# Reid_Orthotic_v2_MUX.net
KiCad netlist of a schematic drawn in Altium Designer
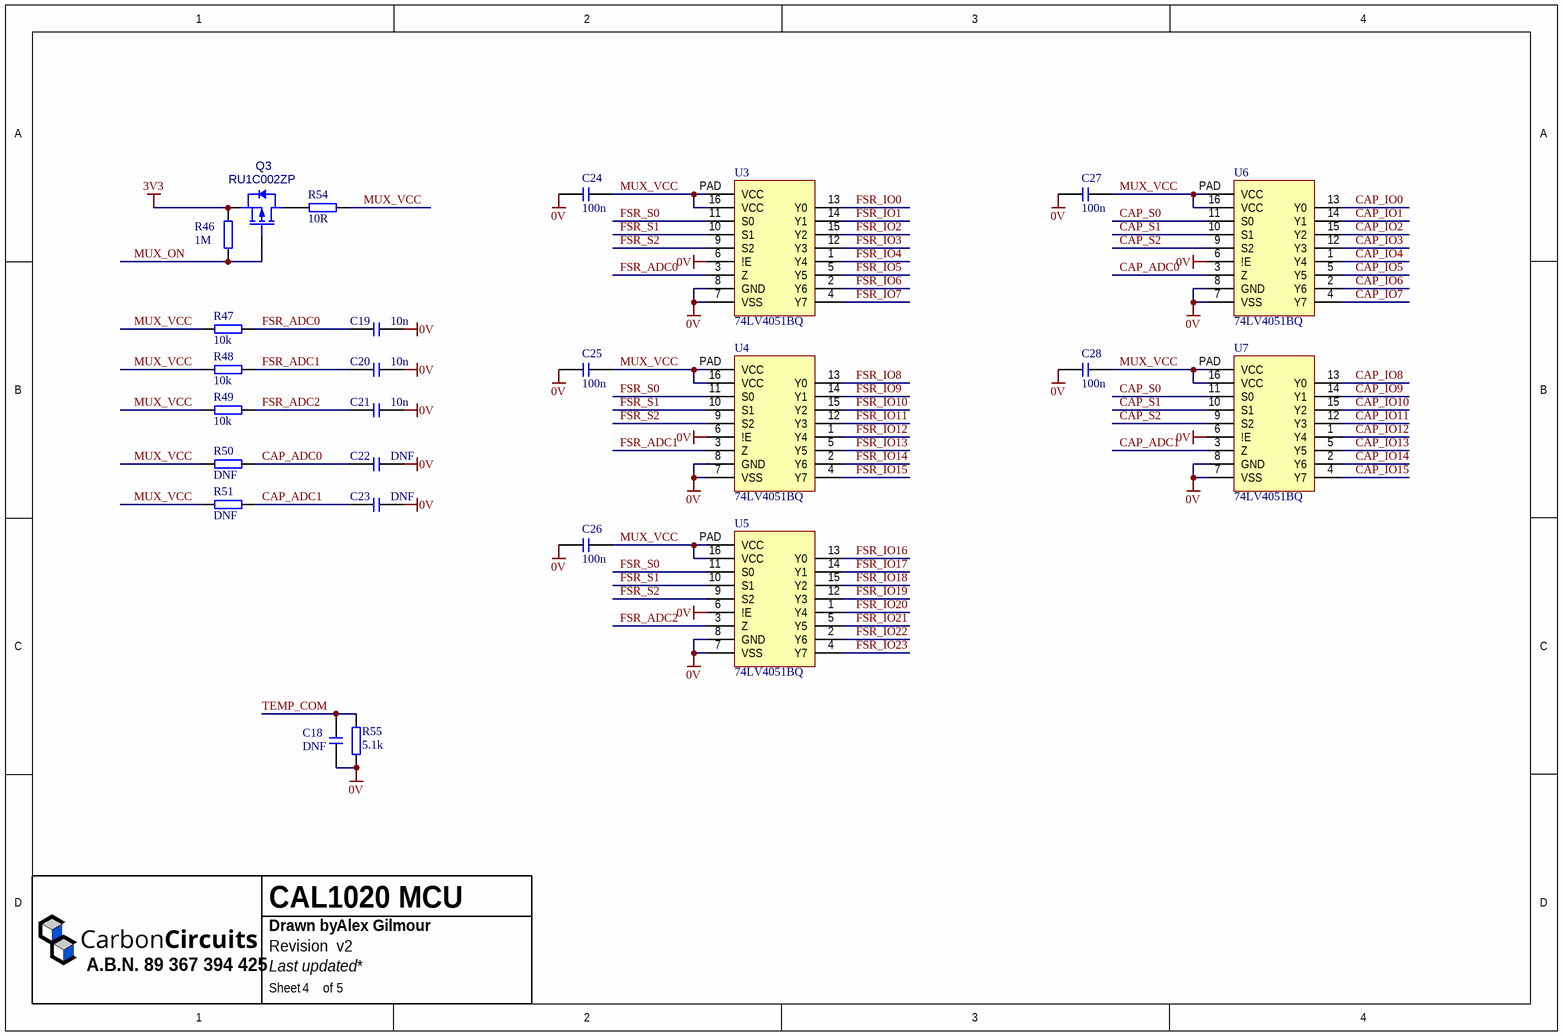
[diagram p0: Reid Orthotic v2 MUX.SchDoc]

(export (version "E")
  (design (tool "Eeschema 10.0.6"))
  (components
    (comp (ref "C18")
      (value "DNF")
      (footprint "0402 CAP HD")
      (libsource (lib "zoo589 PCB Library") (part "Capacitor"))
    )
    (comp (ref "C19")
      (value "10n")
      (footprint "0402 CAP HD")
      (libsource (lib "zoo589 PCB Library") (part "Capacitor"))
    )
    (comp (ref "C20")
      (value "10n")
      (footprint "0402 CAP HD")
      (libsource (lib "zoo589 PCB Library") (part "Capacitor"))
    )
    (comp (ref "C21")
      (value "10n")
      (footprint "0402 CAP HD")
      (libsource (lib "zoo589 PCB Library") (part "Capacitor"))
    )
    (comp (ref "C22")
      (value "DNF")
      (footprint "0402 CAP HD")
      (libsource (lib "zoo589 PCB Library") (part "Capacitor"))
    )
    (comp (ref "C23")
      (value "DNF")
      (footprint "0402 CAP HD")
      (libsource (lib "zoo589 PCB Library") (part "Capacitor"))
    )
    (comp (ref "C24")
      (value "100n")
      (footprint "0402 CAP HD")
      (libsource (lib "zoo589 PCB Library") (part "Capacitor"))
    )
    (comp (ref "C25")
      (value "100n")
      (footprint "0402 CAP HD")
      (libsource (lib "zoo589 PCB Library") (part "Capacitor"))
    )
    (comp (ref "C26")
      (value "100n")
      (footprint "0402 CAP HD")
      (libsource (lib "zoo589 PCB Library") (part "Capacitor"))
    )
    (comp (ref "C27")
      (value "100n")
      (footprint "0402 CAP HD")
      (libsource (lib "zoo589 PCB Library") (part "Capacitor"))
    )
    (comp (ref "C28")
      (value "100n")
      (footprint "0402 CAP HD")
      (libsource (lib "zoo589 PCB Library") (part "Capacitor"))
    )
    (comp (ref "Q3")
      (value "RU1C002ZP")
      (footprint "SOT323")
      (libsource (lib "zoo589 PCB Library") (part "MOSFET PCH"))
    )
    (comp (ref "R46")
      (value "1M")
      (footprint "0402 RES HD")
      (libsource (lib "zoo589 PCB Library") (part "Resistor"))
    )
    (comp (ref "R47")
      (value "10k")
      (footprint "0402 RES HD")
      (libsource (lib "zoo589 PCB Library") (part "Resistor"))
    )
    (comp (ref "R48")
      (value "10k")
      (footprint "0402 RES HD")
      (libsource (lib "zoo589 PCB Library") (part "Resistor"))
    )
    (comp (ref "R49")
      (value "10k")
      (footprint "0402 RES HD")
      (libsource (lib "zoo589 PCB Library") (part "Resistor"))
    )
    (comp (ref "R50")
      (value "DNF")
      (footprint "0402 RES HD")
      (libsource (lib "zoo589 PCB Library") (part "Resistor"))
    )
    (comp (ref "R51")
      (value "DNF")
      (footprint "0402 RES HD")
      (libsource (lib "zoo589 PCB Library") (part "Resistor"))
    )
    (comp (ref "R54")
      (value "10R")
      (footprint "0603 RES HD")
      (libsource (lib "zoo589 PCB Library") (part "Resistor"))
    )
    (comp (ref "R55")
      (value "5.1k")
      (footprint "0402 RES HD")
      (libsource (lib "zoo589 PCB Library") (part "Resistor"))
    )
    (comp (ref "U3")
      (value "74LV4051BQ")
      (footprint "74LV4051BQ")
      (libsource (lib "CarbonCircuits Part Library") (part "74HC4051BQ"))
    )
    (comp (ref "U4")
      (value "74LV4051BQ")
      (footprint "74LV4051BQ")
      (libsource (lib "CarbonCircuits Part Library") (part "74HC4051BQ"))
    )
    (comp (ref "U5")
      (value "74LV4051BQ")
      (footprint "74LV4051BQ")
      (libsource (lib "CarbonCircuits Part Library") (part "74HC4051BQ"))
    )
    (comp (ref "U6")
      (value "74LV4051BQ")
      (footprint "74LV4051BQ")
      (libsource (lib "CarbonCircuits Part Library") (part "74HC4051BQ"))
    )
    (comp (ref "U7")
      (value "74LV4051BQ")
      (footprint "74LV4051BQ")
      (libsource (lib "CarbonCircuits Part Library") (part "74HC4051BQ"))
    )
  )
  (nets
    (net (code "1") (name "/CAP_ADC0") (class "Default")
      (node (ref "C22") (pin "1") (pinfunction "1_1") (pintype "passive"))
      (node (ref "R50") (pin "1") (pinfunction "1_1") (pintype "passive"))
      (node (ref "U6") (pin "3") (pinfunction "Z_3") (pintype "passive"))
    )
    (net (code "2") (name "/CAP_ADC1") (class "Default")
      (node (ref "C23") (pin "1") (pinfunction "1_1") (pintype "passive"))
      (node (ref "R51") (pin "1") (pinfunction "1_1") (pintype "passive"))
      (node (ref "U7") (pin "3") (pinfunction "Z_3") (pintype "passive"))
    )
    (net (code "3") (name "/CAP_IO0") (class "Default")
      (node (ref "U6") (pin "13") (pinfunction "Y0_13") (pintype "passive"))
    )
    (net (code "4") (name "/CAP_IO1") (class "Default")
      (node (ref "U6") (pin "14") (pinfunction "Y1_14") (pintype "passive"))
    )
    (net (code "5") (name "/CAP_IO2") (class "Default")
      (node (ref "U6") (pin "15") (pinfunction "Y2_15") (pintype "passive"))
    )
    (net (code "6") (name "/CAP_IO3") (class "Default")
      (node (ref "U6") (pin "12") (pinfunction "Y3_12") (pintype "passive"))
    )
    (net (code "7") (name "/CAP_IO4") (class "Default")
      (node (ref "U6") (pin "1") (pinfunction "Y4_1") (pintype "passive"))
    )
    (net (code "8") (name "/CAP_IO5") (class "Default")
      (node (ref "U6") (pin "5") (pinfunction "Y5_5") (pintype "passive"))
    )
    (net (code "9") (name "/CAP_IO6") (class "Default")
      (node (ref "U6") (pin "2") (pinfunction "Y6_2") (pintype "passive"))
    )
    (net (code "10") (name "/CAP_IO7") (class "Default")
      (node (ref "U6") (pin "4") (pinfunction "Y7_4") (pintype "passive"))
    )
    (net (code "11") (name "/CAP_IO8") (class "Default")
      (node (ref "U7") (pin "13") (pinfunction "Y0_13") (pintype "passive"))
    )
    (net (code "12") (name "/CAP_IO9") (class "Default")
      (node (ref "U7") (pin "14") (pinfunction "Y1_14") (pintype "passive"))
    )
    (net (code "13") (name "/CAP_IO10") (class "Default")
      (node (ref "U7") (pin "15") (pinfunction "Y2_15") (pintype "passive"))
    )
    (net (code "14") (name "/CAP_IO11") (class "Default")
      (node (ref "U7") (pin "12") (pinfunction "Y3_12") (pintype "passive"))
    )
    (net (code "15") (name "/CAP_IO12") (class "Default")
      (node (ref "U7") (pin "1") (pinfunction "Y4_1") (pintype "passive"))
    )
    (net (code "16") (name "/CAP_IO13") (class "Default")
      (node (ref "U7") (pin "5") (pinfunction "Y5_5") (pintype "passive"))
    )
    (net (code "17") (name "/CAP_IO14") (class "Default")
      (node (ref "U7") (pin "2") (pinfunction "Y6_2") (pintype "passive"))
    )
    (net (code "18") (name "/CAP_IO15") (class "Default")
      (node (ref "U7") (pin "4") (pinfunction "Y7_4") (pintype "passive"))
    )
    (net (code "19") (name "/CAP_S0") (class "Default")
      (node (ref "U6") (pin "11") (pinfunction "S0_11") (pintype "passive"))
      (node (ref "U7") (pin "11") (pinfunction "S0_11") (pintype "passive"))
    )
    (net (code "20") (name "/CAP_S1") (class "Default")
      (node (ref "U6") (pin "10") (pinfunction "S1_10") (pintype "passive"))
      (node (ref "U7") (pin "10") (pinfunction "S1_10") (pintype "passive"))
    )
    (net (code "21") (name "/CAP_S2") (class "Default")
      (node (ref "U6") (pin "9") (pinfunction "S2_9") (pintype "passive"))
      (node (ref "U7") (pin "9") (pinfunction "S2_9") (pintype "passive"))
    )
    (net (code "22") (name "/FSR_ADC0") (class "Default")
      (node (ref "C19") (pin "1") (pinfunction "1_1") (pintype "passive"))
      (node (ref "R47") (pin "1") (pinfunction "1_1") (pintype "passive"))
      (node (ref "U3") (pin "3") (pinfunction "Z_3") (pintype "passive"))
    )
    (net (code "23") (name "/FSR_ADC1") (class "Default")
      (node (ref "C20") (pin "1") (pinfunction "1_1") (pintype "passive"))
      (node (ref "R48") (pin "1") (pinfunction "1_1") (pintype "passive"))
      (node (ref "U4") (pin "3") (pinfunction "Z_3") (pintype "passive"))
    )
    (net (code "24") (name "/FSR_ADC2") (class "Default")
      (node (ref "C21") (pin "1") (pinfunction "1_1") (pintype "passive"))
      (node (ref "R49") (pin "1") (pinfunction "1_1") (pintype "passive"))
      (node (ref "U5") (pin "3") (pinfunction "Z_3") (pintype "passive"))
    )
    (net (code "25") (name "/FSR_IO0") (class "Default")
      (node (ref "U3") (pin "13") (pinfunction "Y0_13") (pintype "passive"))
    )
    (net (code "26") (name "/FSR_IO1") (class "Default")
      (node (ref "U3") (pin "14") (pinfunction "Y1_14") (pintype "passive"))
    )
    (net (code "27") (name "/FSR_IO2") (class "Default")
      (node (ref "U3") (pin "15") (pinfunction "Y2_15") (pintype "passive"))
    )
    (net (code "28") (name "/FSR_IO3") (class "Default")
      (node (ref "U3") (pin "12") (pinfunction "Y3_12") (pintype "passive"))
    )
    (net (code "29") (name "/FSR_IO4") (class "Default")
      (node (ref "U3") (pin "1") (pinfunction "Y4_1") (pintype "passive"))
    )
    (net (code "30") (name "/FSR_IO5") (class "Default")
      (node (ref "U3") (pin "5") (pinfunction "Y5_5") (pintype "passive"))
    )
    (net (code "31") (name "/FSR_IO6") (class "Default")
      (node (ref "U3") (pin "2") (pinfunction "Y6_2") (pintype "passive"))
    )
    (net (code "32") (name "/FSR_IO7") (class "Default")
      (node (ref "U3") (pin "4") (pinfunction "Y7_4") (pintype "passive"))
    )
    (net (code "33") (name "/FSR_IO8") (class "Default")
      (node (ref "U4") (pin "13") (pinfunction "Y0_13") (pintype "passive"))
    )
    (net (code "34") (name "/FSR_IO9") (class "Default")
      (node (ref "U4") (pin "14") (pinfunction "Y1_14") (pintype "passive"))
    )
    (net (code "35") (name "/FSR_IO10") (class "Default")
      (node (ref "U4") (pin "15") (pinfunction "Y2_15") (pintype "passive"))
    )
    (net (code "36") (name "/FSR_IO11") (class "Default")
      (node (ref "U4") (pin "12") (pinfunction "Y3_12") (pintype "passive"))
    )
    (net (code "37") (name "/FSR_IO12") (class "Default")
      (node (ref "U4") (pin "1") (pinfunction "Y4_1") (pintype "passive"))
    )
    (net (code "38") (name "/FSR_IO13") (class "Default")
      (node (ref "U4") (pin "5") (pinfunction "Y5_5") (pintype "passive"))
    )
    (net (code "39") (name "/FSR_IO14") (class "Default")
      (node (ref "U4") (pin "2") (pinfunction "Y6_2") (pintype "passive"))
    )
    (net (code "40") (name "/FSR_IO15") (class "Default")
      (node (ref "U4") (pin "4") (pinfunction "Y7_4") (pintype "passive"))
    )
    (net (code "41") (name "/FSR_IO16") (class "Default")
      (node (ref "U5") (pin "13") (pinfunction "Y0_13") (pintype "passive"))
    )
    (net (code "42") (name "/FSR_IO17") (class "Default")
      (node (ref "U5") (pin "14") (pinfunction "Y1_14") (pintype "passive"))
    )
    (net (code "43") (name "/FSR_IO18") (class "Default")
      (node (ref "U5") (pin "15") (pinfunction "Y2_15") (pintype "passive"))
    )
    (net (code "44") (name "/FSR_IO19") (class "Default")
      (node (ref "U5") (pin "12") (pinfunction "Y3_12") (pintype "passive"))
    )
    (net (code "45") (name "/FSR_IO20") (class "Default")
      (node (ref "U5") (pin "1") (pinfunction "Y4_1") (pintype "passive"))
    )
    (net (code "46") (name "/FSR_IO21") (class "Default")
      (node (ref "U5") (pin "5") (pinfunction "Y5_5") (pintype "passive"))
    )
    (net (code "47") (name "/FSR_IO22") (class "Default")
      (node (ref "U5") (pin "2") (pinfunction "Y6_2") (pintype "passive"))
    )
    (net (code "48") (name "/FSR_IO23") (class "Default")
      (node (ref "U5") (pin "4") (pinfunction "Y7_4") (pintype "passive"))
    )
    (net (code "49") (name "/FSR_S0") (class "Default")
      (node (ref "U3") (pin "11") (pinfunction "S0_11") (pintype "passive"))
      (node (ref "U4") (pin "11") (pinfunction "S0_11") (pintype "passive"))
      (node (ref "U5") (pin "11") (pinfunction "S0_11") (pintype "passive"))
    )
    (net (code "50") (name "/FSR_S1") (class "Default")
      (node (ref "U3") (pin "10") (pinfunction "S1_10") (pintype "passive"))
      (node (ref "U4") (pin "10") (pinfunction "S1_10") (pintype "passive"))
      (node (ref "U5") (pin "10") (pinfunction "S1_10") (pintype "passive"))
    )
    (net (code "51") (name "/FSR_S2") (class "Default")
      (node (ref "U3") (pin "9") (pinfunction "S2_9") (pintype "passive"))
      (node (ref "U4") (pin "9") (pinfunction "S2_9") (pintype "passive"))
      (node (ref "U5") (pin "9") (pinfunction "S2_9") (pintype "passive"))
    )
    (net (code "52") (name "/MUX_ON") (class "Default")
      (node (ref "Q3") (pin "1") (pinfunction "G_1") (pintype "passive"))
      (node (ref "R46") (pin "1") (pinfunction "1_1") (pintype "passive"))
    )
    (net (code "53") (name "/MUX_VCC") (class "Default")
      (node (ref "C24") (pin "2") (pinfunction "2_2") (pintype "passive"))
      (node (ref "C25") (pin "2") (pinfunction "2_2") (pintype "passive"))
      (node (ref "C26") (pin "2") (pinfunction "2_2") (pintype "passive"))
      (node (ref "C27") (pin "2") (pinfunction "2_2") (pintype "passive"))
      (node (ref "C28") (pin "2") (pinfunction "2_2") (pintype "passive"))
      (node (ref "R47") (pin "2") (pinfunction "2_2") (pintype "passive"))
      (node (ref "R48") (pin "2") (pinfunction "2_2") (pintype "passive"))
      (node (ref "R49") (pin "2") (pinfunction "2_2") (pintype "passive"))
      (node (ref "R50") (pin "2") (pinfunction "2_2") (pintype "passive"))
      (node (ref "R51") (pin "2") (pinfunction "2_2") (pintype "passive"))
      (node (ref "R54") (pin "1") (pinfunction "1_1") (pintype "passive"))
      (node (ref "U3") (pin "16") (pinfunction "VCC_16") (pintype "passive"))
      (node (ref "U3") (pin "PAD") (pinfunction "VCC_PAD") (pintype "passive"))
      (node (ref "U4") (pin "16") (pinfunction "VCC_16") (pintype "passive"))
      (node (ref "U4") (pin "PAD") (pinfunction "VCC_PAD") (pintype "passive"))
      (node (ref "U5") (pin "16") (pinfunction "VCC_16") (pintype "passive"))
      (node (ref "U5") (pin "PAD") (pinfunction "VCC_PAD") (pintype "passive"))
      (node (ref "U6") (pin "16") (pinfunction "VCC_16") (pintype "passive"))
      (node (ref "U6") (pin "PAD") (pinfunction "VCC_PAD") (pintype "passive"))
      (node (ref "U7") (pin "16") (pinfunction "VCC_16") (pintype "passive"))
      (node (ref "U7") (pin "PAD") (pinfunction "VCC_PAD") (pintype "passive"))
    )
    (net (code "54") (name "/TEMP_COM") (class "Default")
      (node (ref "C18") (pin "1") (pinfunction "1_1") (pintype "passive"))
      (node (ref "R55") (pin "1") (pinfunction "1_1") (pintype "passive"))
    )
    (net (code "55") (name "0V") (class "Default")
      (node (ref "C18") (pin "2") (pinfunction "2_2") (pintype "passive"))
      (node (ref "C19") (pin "2") (pinfunction "2_2") (pintype "passive"))
      (node (ref "C20") (pin "2") (pinfunction "2_2") (pintype "passive"))
      (node (ref "C21") (pin "2") (pinfunction "2_2") (pintype "passive"))
      (node (ref "C22") (pin "2") (pinfunction "2_2") (pintype "passive"))
      (node (ref "C23") (pin "2") (pinfunction "2_2") (pintype "passive"))
      (node (ref "C24") (pin "1") (pinfunction "1_1") (pintype "passive"))
      (node (ref "C25") (pin "1") (pinfunction "1_1") (pintype "passive"))
      (node (ref "C26") (pin "1") (pinfunction "1_1") (pintype "passive"))
      (node (ref "C27") (pin "1") (pinfunction "1_1") (pintype "passive"))
      (node (ref "C28") (pin "1") (pinfunction "1_1") (pintype "passive"))
      (node (ref "R55") (pin "2") (pinfunction "2_2") (pintype "passive"))
      (node (ref "U3") (pin "6") (pinfunction "!E_6") (pintype "passive"))
      (node (ref "U3") (pin "7") (pinfunction "VSS_7") (pintype "passive"))
      (node (ref "U3") (pin "8") (pinfunction "GND_8") (pintype "passive"))
      (node (ref "U4") (pin "6") (pinfunction "!E_6") (pintype "passive"))
      (node (ref "U4") (pin "7") (pinfunction "VSS_7") (pintype "passive"))
      (node (ref "U4") (pin "8") (pinfunction "GND_8") (pintype "passive"))
      (node (ref "U5") (pin "6") (pinfunction "!E_6") (pintype "passive"))
      (node (ref "U5") (pin "7") (pinfunction "VSS_7") (pintype "passive"))
      (node (ref "U5") (pin "8") (pinfunction "GND_8") (pintype "passive"))
      (node (ref "U6") (pin "6") (pinfunction "!E_6") (pintype "passive"))
      (node (ref "U6") (pin "7") (pinfunction "VSS_7") (pintype "passive"))
      (node (ref "U6") (pin "8") (pinfunction "GND_8") (pintype "passive"))
      (node (ref "U7") (pin "6") (pinfunction "!E_6") (pintype "passive"))
      (node (ref "U7") (pin "7") (pinfunction "VSS_7") (pintype "passive"))
      (node (ref "U7") (pin "8") (pinfunction "GND_8") (pintype "passive"))
    )
    (net (code "56") (name "3V3") (class "Default")
      (node (ref "Q3") (pin "2") (pinfunction "S_2") (pintype "passive"))
      (node (ref "R46") (pin "2") (pinfunction "2_2") (pintype "passive"))
    )
    (net (code "57") (name "Net-(Q3-D)") (class "Default")
      (node (ref "Q3") (pin "3") (pinfunction "D_3") (pintype "passive"))
      (node (ref "R54") (pin "2") (pinfunction "2_2") (pintype "passive"))
    )
  )
)
